# main_board_gen_2.net
KiCad netlist of a schematic drawn in Altium Designer
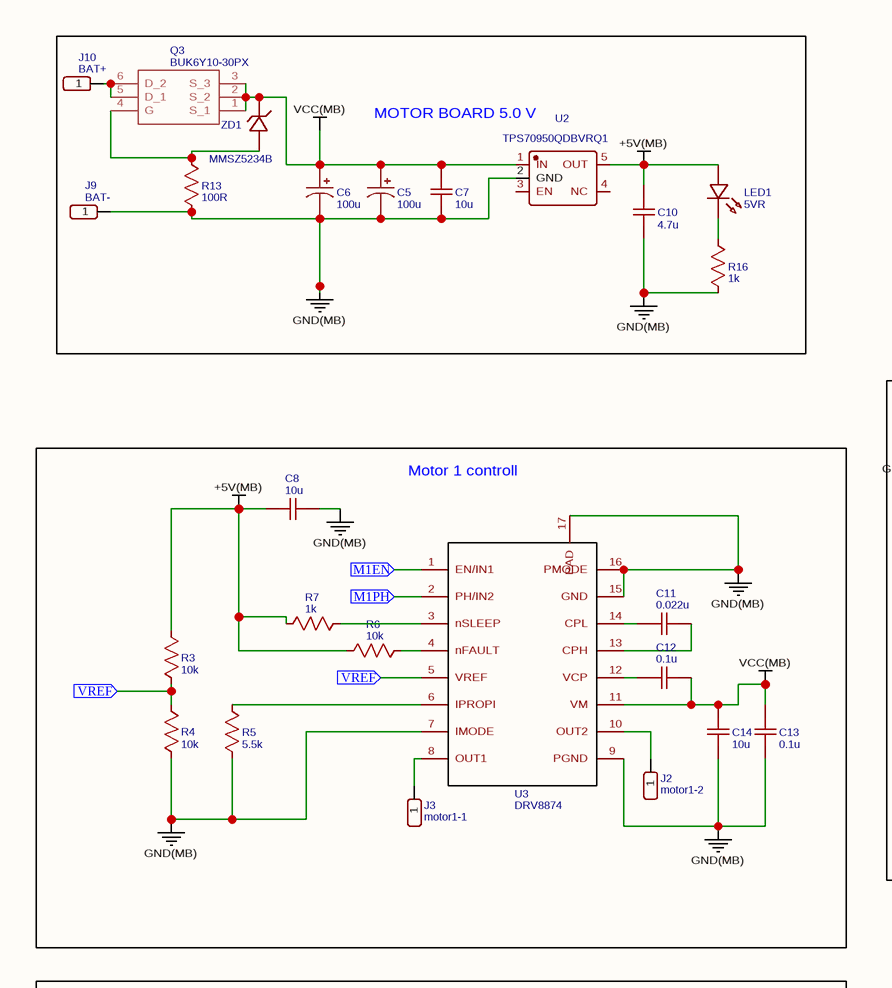
[diagram p0: main_board gen 2.schdoc, top left]
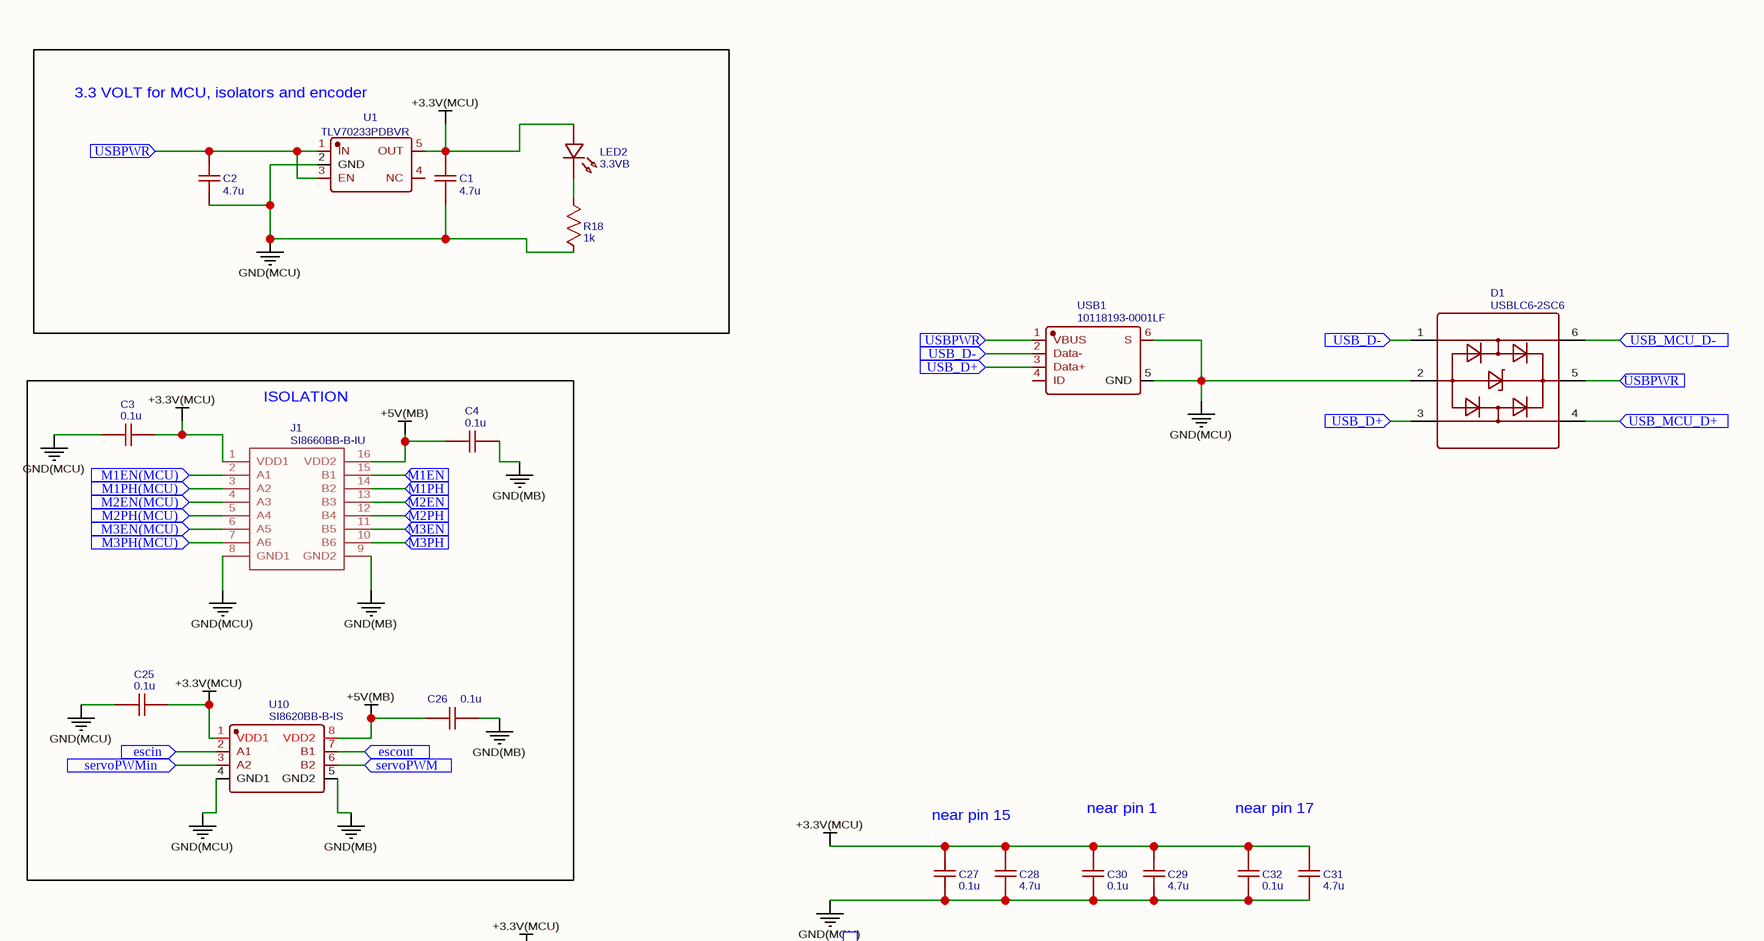
[diagram p1: main_board gen 2.schdoc, top right]
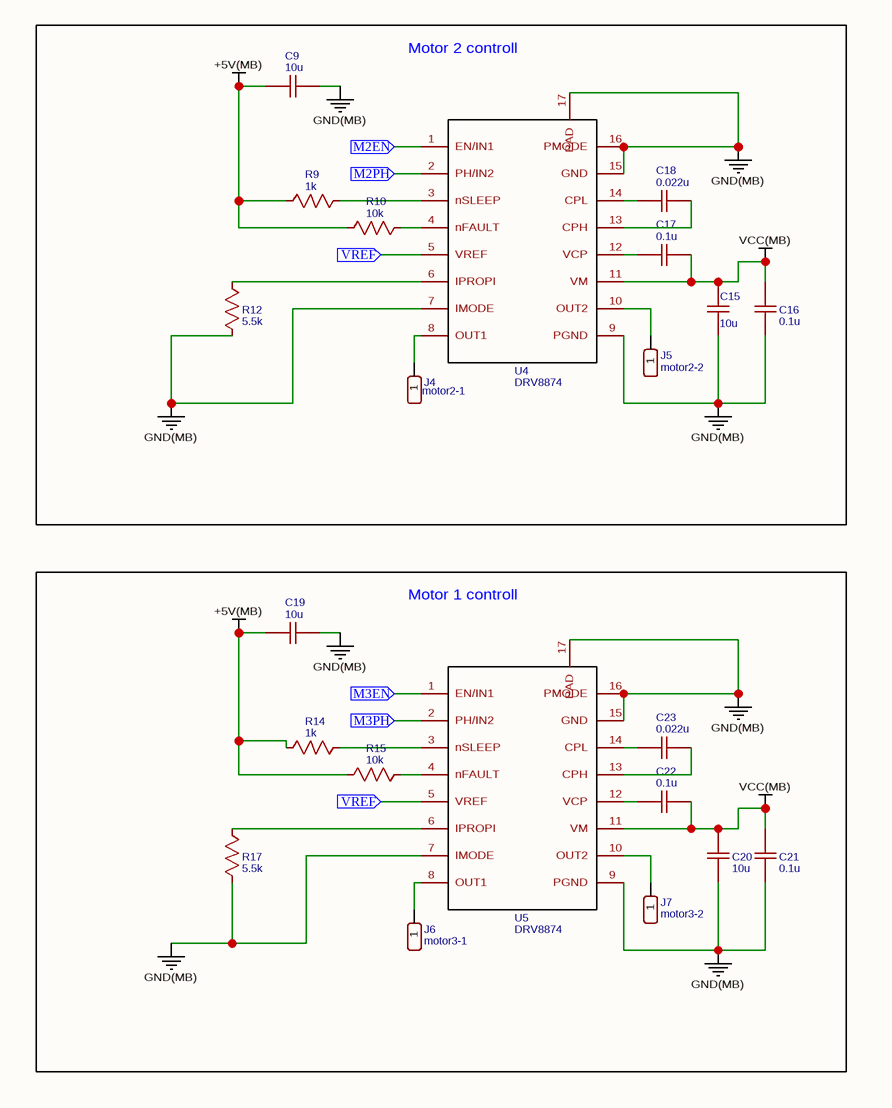
[diagram p2: main_board gen 2.schdoc, bottom left]
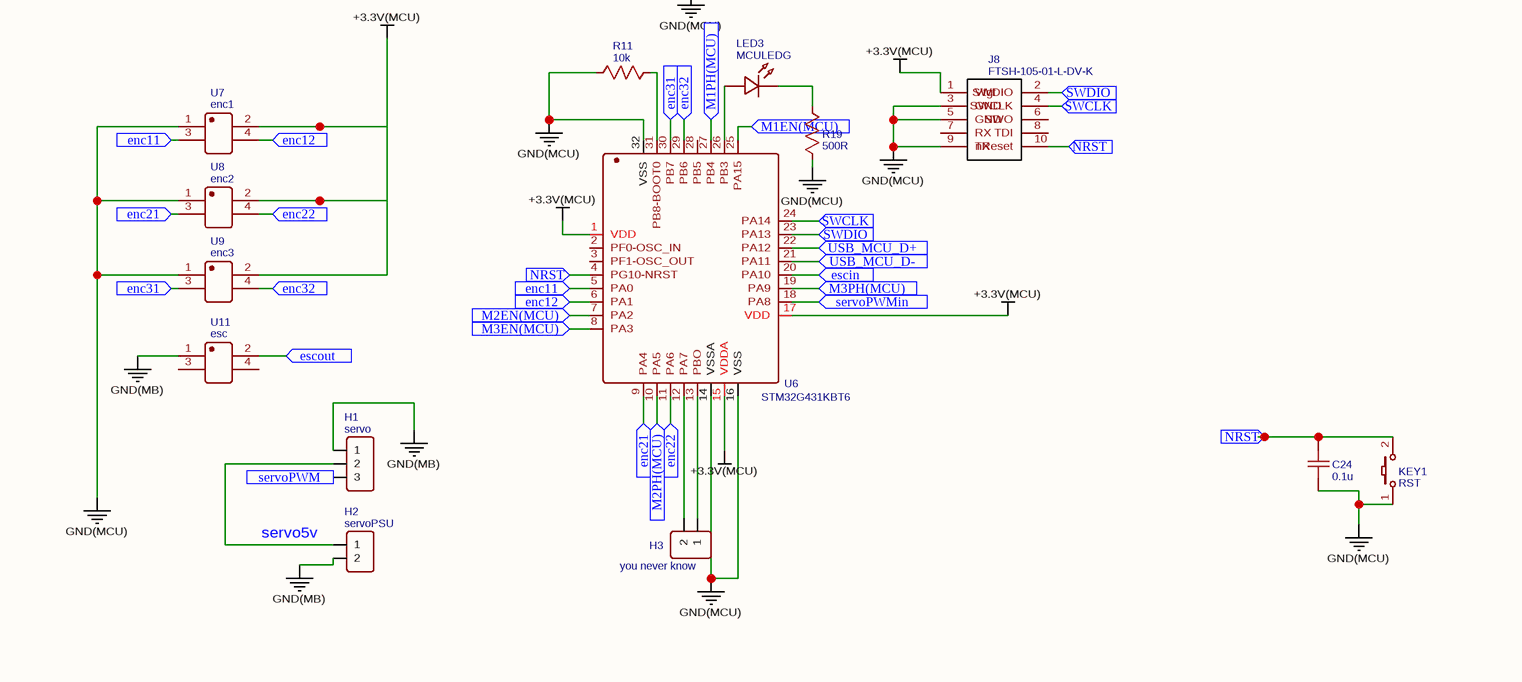
[diagram p3: main_board gen 2.schdoc, bottom right]

(export (version "E")
  (design (tool "Eeschema 10.0.6"))
  (components
    (comp (ref "C1")
      (value "4.7u")
      (fields (field (name "CONTRIBUTOR") "LCEDA_Lib"))
      (libsource (lib "altium-import") (part "root_1_4.7u_"))
    )
    (comp (ref "C2")
      (value "4.7u")
      (fields (field (name "CONTRIBUTOR") "LCEDA_Lib"))
      (libsource (lib "altium-import") (part "root_1_4.7u_"))
    )
    (comp (ref "C3")
      (value "0.1u")
      (fields (field (name "CONTRIBUTOR") "LCEDA_Lib"))
      (libsource (lib "altium-import") (part "root_2_0.1u_"))
    )
    (comp (ref "C4")
      (value "0.1u")
      (fields (field (name "CONTRIBUTOR") "LCEDA_Lib"))
      (libsource (lib "altium-import") (part "root_2_0.1u_"))
    )
    (comp (ref "C5")
      (value "100u")
      (fields (field (name "CONTRIBUTOR") "LCEDA_Lib"))
      (libsource (lib "altium-import") (part "root_3_100u_"))
    )
    (comp (ref "C6")
      (value "100u")
      (fields (field (name "CONTRIBUTOR") "LCEDA_Lib"))
      (libsource (lib "altium-import") (part "root_3_100u_"))
    )
    (comp (ref "C7")
      (value "10u")
      (fields (field (name "CONTRIBUTOR") "LCEDA_Lib"))
      (libsource (lib "altium-import") (part "root_1_10u_"))
    )
    (comp (ref "C8")
      (value "10u")
      (fields (field (name "CONTRIBUTOR") "LCEDA_Lib"))
      (libsource (lib "altium-import") (part "root_0_10u_"))
    )
    (comp (ref "C9")
      (value "10u")
      (fields (field (name "CONTRIBUTOR") "LCEDA_Lib"))
      (libsource (lib "altium-import") (part "root_0_10u_"))
    )
    (comp (ref "C10")
      (value "4.7u")
      (fields (field (name "CONTRIBUTOR") "LCEDA_Lib"))
      (libsource (lib "altium-import") (part "root_1_4.7u_"))
    )
    (comp (ref "C11")
      (value "0.022u")
      (fields (field (name "CONTRIBUTOR") "LCEDA_Lib"))
      (libsource (lib "altium-import") (part "root_0_0.022u_"))
    )
    (comp (ref "C12")
      (value "0.1u")
      (fields (field (name "CONTRIBUTOR") "LCEDA_Lib"))
      (libsource (lib "altium-import") (part "root_0_0.1u_"))
    )
    (comp (ref "C13")
      (value "0.1u")
      (fields (field (name "CONTRIBUTOR") "LCEDA_Lib"))
      (libsource (lib "altium-import") (part "root_1_0.1u_"))
    )
    (comp (ref "C14")
      (value "10u")
      (fields (field (name "CONTRIBUTOR") "LCEDA_Lib"))
      (libsource (lib "altium-import") (part "root_1_10u_"))
    )
    (comp (ref "C15")
      (value "10u")
      (fields (field (name "CONTRIBUTOR") "LCEDA_Lib"))
      (libsource (lib "altium-import") (part "root_1_10u_"))
    )
    (comp (ref "C16")
      (value "0.1u")
      (fields (field (name "CONTRIBUTOR") "LCEDA_Lib"))
      (libsource (lib "altium-import") (part "root_1_0.1u_"))
    )
    (comp (ref "C17")
      (value "0.1u")
      (fields (field (name "CONTRIBUTOR") "LCEDA_Lib"))
      (libsource (lib "altium-import") (part "root_0_0.1u_"))
    )
    (comp (ref "C18")
      (value "0.022u")
      (fields (field (name "CONTRIBUTOR") "LCEDA_Lib"))
      (libsource (lib "altium-import") (part "root_0_0.022u_"))
    )
    (comp (ref "C19")
      (value "10u")
      (fields (field (name "CONTRIBUTOR") "LCEDA_Lib"))
      (libsource (lib "altium-import") (part "root_0_10u_"))
    )
    (comp (ref "C20")
      (value "10u")
      (fields (field (name "CONTRIBUTOR") "LCEDA_Lib"))
      (libsource (lib "altium-import") (part "root_1_10u_"))
    )
    (comp (ref "C21")
      (value "0.1u")
      (fields (field (name "CONTRIBUTOR") "LCEDA_Lib"))
      (libsource (lib "altium-import") (part "root_1_0.1u_"))
    )
    (comp (ref "C22")
      (value "0.1u")
      (fields (field (name "CONTRIBUTOR") "LCEDA_Lib"))
      (libsource (lib "altium-import") (part "root_0_0.1u_"))
    )
    (comp (ref "C23")
      (value "0.022u")
      (fields (field (name "CONTRIBUTOR") "LCEDA_Lib"))
      (libsource (lib "altium-import") (part "root_0_0.022u_"))
    )
    (comp (ref "C24")
      (value "0.1u")
      (fields (field (name "CONTRIBUTOR") "LCEDA_Lib"))
      (libsource (lib "altium-import") (part "root_1_0.1u_"))
    )
    (comp (ref "C25")
      (value "0.1u")
      (fields (field (name "CONTRIBUTOR") "LCEDA_Lib"))
      (libsource (lib "altium-import") (part "root_2_0.1u_"))
    )
    (comp (ref "C26")
      (value "0.1u")
      (fields (field (name "CONTRIBUTOR") "LCEDA_Lib"))
      (libsource (lib "altium-import") (part "root_2_0.1u_"))
    )
    (comp (ref "C27")
      (value "0.1u")
      (fields (field (name "CONTRIBUTOR") "LCEDA_Lib"))
      (libsource (lib "altium-import") (part "root_1_0.1u_"))
    )
    (comp (ref "C28")
      (value "4.7u")
      (fields (field (name "CONTRIBUTOR") "LCEDA_Lib"))
      (libsource (lib "altium-import") (part "root_1_4.7u_"))
    )
    (comp (ref "C29")
      (value "4.7u")
      (fields (field (name "CONTRIBUTOR") "LCEDA_Lib"))
      (libsource (lib "altium-import") (part "root_1_4.7u_"))
    )
    (comp (ref "C30")
      (value "0.1u")
      (fields (field (name "CONTRIBUTOR") "LCEDA_Lib"))
      (libsource (lib "altium-import") (part "root_1_0.1u_"))
    )
    (comp (ref "C31")
      (value "4.7u")
      (fields (field (name "CONTRIBUTOR") "LCEDA_Lib"))
      (libsource (lib "altium-import") (part "root_1_4.7u_"))
    )
    (comp (ref "C32")
      (value "0.1u")
      (fields (field (name "CONTRIBUTOR") "LCEDA_Lib"))
      (libsource (lib "altium-import") (part "root_1_0.1u_"))
    )
    (comp (ref "D1")
      (value "USBLC6-2SC6")
      (fields (field (name "BOM_SUPPLIER PART") "C7519"))
      (libsource (lib "altium-import") (part "root_0_USBLC6-2SC6_"))
    )
    (comp (ref "H1")
      (value "servo")
      (fields (field (name "BOM_SUPPLIER PART") "C146690") (field (name "CONTRIBUTOR") "LCEDA_Lib"))
      (libsource (lib "altium-import") (part "root_0_servo_"))
    )
    (comp (ref "H2")
      (value "servoPSU")
      (fields (field (name "BOM_SUPPLIER PART") "C49661") (field (name "CONTRIBUTOR") "LCEDA_Lib"))
      (libsource (lib "altium-import") (part "root_0_servoPSU_"))
    )
    (comp (ref "H3")
      (value "you never know")
      (fields (field (name "BOM_SUPPLIER PART") "C49661") (field (name "CONTRIBUTOR") "LCEDA_Lib"))
      (libsource (lib "altium-import") (part "root_3_you never know_"))
    )
    (comp (ref "J1")
      (value "SI8660BB-B-IU")
      (fields (field (name "CONTRIBUTOR") "david rizhinashvili"))
      (libsource (lib "altium-import") (part "root_0_SI8660BB-B-IU_"))
    )
    (comp (ref "J2")
      (value "motor1-2")
      (fields (field (name "BOM_SUPPLIER PART") "C81276") (field (name "CONTRIBUTOR") "LCEDA_Lib"))
      (libsource (lib "altium-import") (part "root_3_motor1-2_"))
    )
    (comp (ref "J3")
      (value "motor1-1")
      (fields (field (name "BOM_SUPPLIER PART") "C81276") (field (name "CONTRIBUTOR") "LCEDA_Lib"))
      (libsource (lib "altium-import") (part "root_3_motor1-1_"))
    )
    (comp (ref "J4")
      (value "motor2-1")
      (fields (field (name "BOM_SUPPLIER PART") "C81276") (field (name "CONTRIBUTOR") "LCEDA_Lib"))
      (libsource (lib "altium-import") (part "root_3_motor2-1_"))
    )
    (comp (ref "J5")
      (value "motor2-2")
      (fields (field (name "BOM_SUPPLIER PART") "C81276") (field (name "CONTRIBUTOR") "LCEDA_Lib"))
      (libsource (lib "altium-import") (part "root_3_motor2-2_"))
    )
    (comp (ref "J6")
      (value "motor3-1")
      (fields (field (name "BOM_SUPPLIER PART") "C81276") (field (name "CONTRIBUTOR") "LCEDA_Lib"))
      (libsource (lib "altium-import") (part "root_3_motor3-1_"))
    )
    (comp (ref "J7")
      (value "motor3-2")
      (fields (field (name "BOM_SUPPLIER PART") "C81276") (field (name "CONTRIBUTOR") "LCEDA_Lib"))
      (libsource (lib "altium-import") (part "root_3_motor3-2_"))
    )
    (comp (ref "J8")
      (value "FTSH-105-01-L-DV-K")
      (fields (field (name "BOM_SUPPLIER PART") "SAM8799-ND") (field (name "CONTRIBUTOR") "OBC Gang"))
      (libsource (lib "altium-import") (part "root_0_FTSH-105-01-L-DV-K_"))
    )
    (comp (ref "J9")
      (value "BAT-")
      (fields (field (name "BOM_SUPPLIER PART") "C81276") (field (name "CONTRIBUTOR") "LCEDA_Lib"))
      (libsource (lib "altium-import") (part "root_2_BAT-_"))
    )
    (comp (ref "J10")
      (value "BAT+")
      (fields (field (name "BOM_SUPPLIER PART") "C81276") (field (name "CONTRIBUTOR") "LCEDA_Lib"))
      (libsource (lib "altium-import") (part "root_2_BAT+_"))
    )
    (comp (ref "KEY1")
      (value "RST")
      (fields
        (field (name "BOM_SUPPLIER PART") "C118141")
        (field (name "BOM_MANUFACTURER PART") "K2-1107ST-A4SW-06")
        (field (name "CONTRIBUTOR") "LCEDA_Lib")
      )
      (libsource (lib "altium-import") (part "root_1_RST_"))
    )
    (comp (ref "LED1")
      (value "5VR")
      (fields
        (field (name "BOM_MANUFACTURER PART") "19-217/R6C-AL1M2VY/3T")
        (field (name "BOM_SUPPLIER PART") "C72044")
        (field (name "CONTRIBUTOR") "LCEDA_01")
      )
      (libsource (lib "altium-import") (part "root_3_5VR_"))
    )
    (comp (ref "LED2")
      (value "3.3VB")
      (fields
        (field (name "BOM_MANUFACTURER PART") "19-217/R6C-AL1M2VY/3T")
        (field (name "BOM_SUPPLIER PART") "C72044")
        (field (name "CONTRIBUTOR") "LCEDA_01")
      )
      (libsource (lib "altium-import") (part "root_3_3.3VB_"))
    )
    (comp (ref "LED3")
      (value "MCULEDG")
      (fields
        (field (name "BOM_MANUFACTURER PART") "19-217/R6C-AL1M2VY/3T")
        (field (name "BOM_SUPPLIER PART") "C72044")
        (field (name "CONTRIBUTOR") "LCEDA_01")
      )
      (libsource (lib "altium-import") (part "root_0_MCULEDG_"))
    )
    (comp (ref "Q3")
      (value "BUK6Y10-30PX")
      (fields (field (name "CONTRIBUTOR") "david rizhinashvili"))
      (libsource (lib "altium-import") (part "root_2_BUK6Y10-30PX_"))
    )
    (comp (ref "R3")
      (value "10k")
      (fields (field (name "CONTRIBUTOR") "LCEDA_Lib"))
      (libsource (lib "altium-import") (part "root_3_10k_"))
    )
    (comp (ref "R4")
      (value "10k")
      (fields (field (name "CONTRIBUTOR") "LCEDA_Lib"))
      (libsource (lib "altium-import") (part "root_3_10k_"))
    )
    (comp (ref "R5")
      (value "5.5k")
      (fields (field (name "CONTRIBUTOR") "LCEDA_Lib"))
      (libsource (lib "altium-import") (part "root_1_5.5k_"))
    )
    (comp (ref "R6")
      (value "10k")
      (fields (field (name "CONTRIBUTOR") "LCEDA_Lib"))
      (libsource (lib "altium-import") (part "root_0_10k_"))
    )
    (comp (ref "R7")
      (value "1k")
      (fields (field (name "CONTRIBUTOR") "LCEDA_Lib"))
      (libsource (lib "altium-import") (part "root_0_1k_"))
    )
    (comp (ref "R9")
      (value "1k")
      (fields (field (name "CONTRIBUTOR") "LCEDA_Lib"))
      (libsource (lib "altium-import") (part "root_0_1k_"))
    )
    (comp (ref "R10")
      (value "10k")
      (fields (field (name "CONTRIBUTOR") "LCEDA_Lib"))
      (libsource (lib "altium-import") (part "root_0_10k_"))
    )
    (comp (ref "R11")
      (value "10k")
      (fields (field (name "CONTRIBUTOR") "LCEDA_Lib"))
      (libsource (lib "altium-import") (part "root_0_10k_"))
    )
    (comp (ref "R12")
      (value "5.5k")
      (fields (field (name "CONTRIBUTOR") "LCEDA_Lib"))
      (libsource (lib "altium-import") (part "root_1_5.5k_"))
    )
    (comp (ref "R13")
      (value "100R")
      (fields (field (name "CONTRIBUTOR") "LCEDA_Lib"))
      (libsource (lib "altium-import") (part "root_1_100R_"))
    )
    (comp (ref "R14")
      (value "1k")
      (fields (field (name "CONTRIBUTOR") "LCEDA_Lib"))
      (libsource (lib "altium-import") (part "root_0_1k_"))
    )
    (comp (ref "R15")
      (value "10k")
      (fields (field (name "CONTRIBUTOR") "LCEDA_Lib"))
      (libsource (lib "altium-import") (part "root_0_10k_"))
    )
    (comp (ref "R16")
      (value "1k")
      (fields (field (name "CONTRIBUTOR") "LCEDA_Lib"))
      (libsource (lib "altium-import") (part "root_1_1k_"))
    )
    (comp (ref "R17")
      (value "5.5k")
      (fields (field (name "CONTRIBUTOR") "LCEDA_Lib"))
      (libsource (lib "altium-import") (part "root_1_5.5k_"))
    )
    (comp (ref "R18")
      (value "1k")
      (fields (field (name "CONTRIBUTOR") "LCEDA_Lib"))
      (libsource (lib "altium-import") (part "root_1_1k_"))
    )
    (comp (ref "R19")
      (value "500R")
      (fields (field (name "CONTRIBUTOR") "LCEDA_Lib"))
      (libsource (lib "altium-import") (part "root_1_500R_"))
    )
    (comp (ref "U1")
      (value "TLV70233PDBVR")
      (fields (field (name "BOM_SUPPLIER PART") "C123134") (field (name "CONTRIBUTOR") "LCSC"))
      (libsource (lib "altium-import") (part "root_0_TLV70233PDBVR_"))
    )
    (comp (ref "U2")
      (value "TPS70950QDBVRQ1")
      (fields (field (name "BOM_SUPPLIER PART") "C485909") (field (name "CONTRIBUTOR") "LCSC"))
      (libsource (lib "altium-import") (part "root_0_TPS70950QDBVRQ1_"))
    )
    (comp (ref "U3")
      (value "DRV8874")
      (fields (field (name "CONTRIBUTOR") "Plexus"))
      (libsource (lib "altium-import") (part "root_0_DRV8874_"))
    )
    (comp (ref "U4")
      (value "DRV8874")
      (fields (field (name "CONTRIBUTOR") "Plexus"))
      (libsource (lib "altium-import") (part "root_0_DRV8874_"))
    )
    (comp (ref "U5")
      (value "DRV8874")
      (fields (field (name "CONTRIBUTOR") "Plexus"))
      (libsource (lib "altium-import") (part "root_0_DRV8874_"))
    )
    (comp (ref "U6")
      (value "STM32G431KBT6")
      (fields (field (name "BOM_SUPPLIER PART") "C529357") (field (name "CONTRIBUTOR") "LCSC"))
      (libsource (lib "altium-import") (part "root_0_STM32G431KBT6_"))
    )
    (comp (ref "U7")
      (value "enc1")
      (fields
        (field (name "BOM_SUPPLIER PART") "C306232")
        (field (name "BOM_MANUFACTURER PART") "215079-4")
        (field (name "CONTRIBUTOR") "LCSC")
      )
      (libsource (lib "altium-import") (part "root_0_enc1_"))
    )
    (comp (ref "U8")
      (value "enc2")
      (fields
        (field (name "BOM_SUPPLIER PART") "C306232")
        (field (name "BOM_MANUFACTURER PART") "215079-4")
        (field (name "CONTRIBUTOR") "LCSC")
      )
      (libsource (lib "altium-import") (part "root_0_enc2_"))
    )
    (comp (ref "U9")
      (value "enc3")
      (fields
        (field (name "BOM_SUPPLIER PART") "C306232")
        (field (name "BOM_MANUFACTURER PART") "215079-4")
        (field (name "CONTRIBUTOR") "LCSC")
      )
      (libsource (lib "altium-import") (part "root_0_enc3_"))
    )
    (comp (ref "U10")
      (value "SI8620BB-B-IS")
      (fields (field (name "BOM_SUPPLIER PART") "C430264") (field (name "CONTRIBUTOR") "LCSC"))
      (libsource (lib "altium-import") (part "root_0_SI8620BB-B-IS_"))
    )
    (comp (ref "U11")
      (value "esc")
      (fields
        (field (name "BOM_SUPPLIER PART") "C306232")
        (field (name "BOM_MANUFACTURER PART") "215079-4")
        (field (name "CONTRIBUTOR") "LCSC")
      )
      (libsource (lib "altium-import") (part "root_0_esc_"))
    )
    (comp (ref "USB1")
      (value "10118193-0001LF")
      (fields (field (name "BOM_SUPPLIER PART") "C132562") (field (name "CONTRIBUTOR") "LCSC"))
      (libsource (lib "altium-import") (part "root_0_10118193-0001LF_"))
    )
    (comp (ref "ZD1")
      (value "MMSZ5234B")
      (fields (field (name "BOM_SUPPLIER PART") "C21556"))
      (libsource (lib "altium-import") (part "root_3_MMSZ5234B_"))
    )
  )
  (nets
    (net (code "1") (name "+3.3V(MCU)") (class "Default")
      (node (ref "C1") (pin "2") (pinfunction "2_2") (pintype "passive"))
      (node (ref "C25") (pin "1") (pinfunction "1_1") (pintype "passive"))
      (node (ref "C27") (pin "2") (pinfunction "2_2") (pintype "passive"))
      (node (ref "C28") (pin "2") (pinfunction "2_2") (pintype "passive"))
      (node (ref "C29") (pin "2") (pinfunction "2_2") (pintype "passive"))
      (node (ref "C3") (pin "1") (pinfunction "1_1") (pintype "passive"))
      (node (ref "C30") (pin "2") (pinfunction "2_2") (pintype "passive"))
      (node (ref "C31") (pin "2") (pinfunction "2_2") (pintype "passive"))
      (node (ref "C32") (pin "2") (pinfunction "2_2") (pintype "passive"))
      (node (ref "J1") (pin "1") (pinfunction "VDD1_1") (pintype "passive"))
      (node (ref "J8") (pin "1") (pinfunction "Vtgt_1") (pintype "passive"))
      (node (ref "LED2") (pin "1") (pinfunction "1_1") (pintype "passive"))
      (node (ref "U1") (pin "5") (pinfunction "OUT_5") (pintype "passive"))
      (node (ref "U10") (pin "1") (pinfunction "VDD1_1") (pintype "passive"))
      (node (ref "U6") (pin "1") (pinfunction "VDD_1") (pintype "passive"))
      (node (ref "U6") (pin "15") (pinfunction "VDDA_15") (pintype "passive"))
      (node (ref "U6") (pin "17") (pinfunction "VDD_17") (pintype "passive"))
      (node (ref "U7") (pin "2") (pinfunction "2_2") (pintype "passive"))
      (node (ref "U8") (pin "2") (pinfunction "2_2") (pintype "passive"))
      (node (ref "U9") (pin "2") (pinfunction "2_2") (pintype "passive"))
    )
    (net (code "2") (name "+5V(MB)") (class "Default")
      (node (ref "C10") (pin "2") (pinfunction "2_2") (pintype "passive"))
      (node (ref "C19") (pin "1") (pinfunction "1_1") (pintype "passive"))
      (node (ref "C26") (pin "2") (pinfunction "2_2") (pintype "passive"))
      (node (ref "C4") (pin "2") (pinfunction "2_2") (pintype "passive"))
      (node (ref "C8") (pin "1") (pinfunction "1_1") (pintype "passive"))
      (node (ref "C9") (pin "1") (pinfunction "1_1") (pintype "passive"))
      (node (ref "J1") (pin "16") (pinfunction "VDD2_16") (pintype "passive"))
      (node (ref "LED1") (pin "1") (pinfunction "1_1") (pintype "passive"))
      (node (ref "R10") (pin "1") (pinfunction "1_1") (pintype "passive"))
      (node (ref "R14") (pin "1") (pinfunction "1_1") (pintype "passive"))
      (node (ref "R15") (pin "1") (pinfunction "1_1") (pintype "passive"))
      (node (ref "R3") (pin "1") (pinfunction "1_1") (pintype "passive"))
      (node (ref "R6") (pin "1") (pinfunction "1_1") (pintype "passive"))
      (node (ref "R7") (pin "1") (pinfunction "1_1") (pintype "passive"))
      (node (ref "R9") (pin "1") (pinfunction "1_1") (pintype "passive"))
      (node (ref "U10") (pin "8") (pinfunction "VDD2_8") (pintype "passive"))
      (node (ref "U2") (pin "5") (pinfunction "OUT_5") (pintype "passive"))
    )
    (net (code "3") (name "/M1EN") (class "Default")
      (node (ref "J1") (pin "15") (pinfunction "B1_15") (pintype "passive"))
      (node (ref "U3") (pin "1") (pinfunction "EN/IN1_1") (pintype "passive"))
    )
    (net (code "4") (name "/M1EN(MCU)") (class "Default")
      (node (ref "J1") (pin "2") (pinfunction "A1_2") (pintype "passive"))
      (node (ref "U6") (pin "25") (pinfunction "PA15_25") (pintype "passive"))
    )
    (net (code "5") (name "/M1PH") (class "Default")
      (node (ref "J1") (pin "14") (pinfunction "B2_14") (pintype "passive"))
      (node (ref "U3") (pin "2") (pinfunction "PH/IN2_2") (pintype "passive"))
    )
    (net (code "6") (name "/M1PH(MCU)") (class "Default")
      (node (ref "J1") (pin "3") (pinfunction "A2_3") (pintype "passive"))
      (node (ref "U6") (pin "27") (pinfunction "PB4_27") (pintype "passive"))
    )
    (net (code "7") (name "/M2EN") (class "Default")
      (node (ref "J1") (pin "13") (pinfunction "B3_13") (pintype "passive"))
      (node (ref "U4") (pin "1") (pinfunction "EN/IN1_1") (pintype "passive"))
    )
    (net (code "8") (name "/M2EN(MCU)") (class "Default")
      (node (ref "J1") (pin "4") (pinfunction "A3_4") (pintype "passive"))
      (node (ref "U6") (pin "7") (pinfunction "PA2_7") (pintype "passive"))
    )
    (net (code "9") (name "/M2PH") (class "Default")
      (node (ref "J1") (pin "12") (pinfunction "B4_12") (pintype "passive"))
      (node (ref "U4") (pin "2") (pinfunction "PH/IN2_2") (pintype "passive"))
    )
    (net (code "10") (name "/M2PH(MCU)") (class "Default")
      (node (ref "J1") (pin "5") (pinfunction "A4_5") (pintype "passive"))
      (node (ref "U6") (pin "10") (pinfunction "PA5_10") (pintype "passive"))
    )
    (net (code "11") (name "/M3EN") (class "Default")
      (node (ref "J1") (pin "11") (pinfunction "B5_11") (pintype "passive"))
      (node (ref "U5") (pin "1") (pinfunction "EN/IN1_1") (pintype "passive"))
    )
    (net (code "12") (name "/M3EN(MCU)") (class "Default")
      (node (ref "J1") (pin "6") (pinfunction "A5_6") (pintype "passive"))
      (node (ref "U6") (pin "8") (pinfunction "PA3_8") (pintype "passive"))
    )
    (net (code "13") (name "/M3PH") (class "Default")
      (node (ref "J1") (pin "10") (pinfunction "B6_10") (pintype "passive"))
      (node (ref "U5") (pin "2") (pinfunction "PH/IN2_2") (pintype "passive"))
    )
    (net (code "14") (name "/M3PH(MCU)") (class "Default")
      (node (ref "J1") (pin "7") (pinfunction "A6_7") (pintype "passive"))
      (node (ref "U6") (pin "19") (pinfunction "PA9_19") (pintype "passive"))
    )
    (net (code "15") (name "/NRST") (class "Default")
      (node (ref "C24") (pin "2") (pinfunction "2_2") (pintype "passive"))
      (node (ref "J8") (pin "10") (pinfunction "nReset_10") (pintype "passive"))
      (node (ref "KEY1") (pin "2") (pinfunction "2_2") (pintype "passive"))
      (node (ref "U6") (pin "4") (pinfunction "PG10-NRST_4") (pintype "passive"))
    )
    (net (code "16") (name "/SWCLK") (class "Default")
      (node (ref "J8") (pin "4") (pinfunction "SWCLK_4") (pintype "passive"))
      (node (ref "U6") (pin "24") (pinfunction "PA14_24") (pintype "passive"))
    )
    (net (code "17") (name "/SWDIO") (class "Default")
      (node (ref "J8") (pin "2") (pinfunction "SWDIO_2") (pintype "passive"))
      (node (ref "U6") (pin "23") (pinfunction "PA13_23") (pintype "passive"))
    )
    (net (code "18") (name "/USBPWR") (class "Default")
      (node (ref "C2") (pin "2") (pinfunction "2_2") (pintype "passive"))
      (node (ref "D1") (pin "5") (pinfunction "5_5") (pintype "passive"))
      (node (ref "U1") (pin "1") (pinfunction "IN_1") (pintype "passive"))
      (node (ref "U1") (pin "3") (pinfunction "EN_3") (pintype "passive"))
      (node (ref "USB1") (pin "1") (pinfunction "VBUS_1") (pintype "passive"))
    )
    (net (code "19") (name "/USB_D+") (class "Default")
      (node (ref "D1") (pin "3") (pinfunction "3_3") (pintype "passive"))
      (node (ref "USB1") (pin "3") (pinfunction "Data+_3") (pintype "passive"))
    )
    (net (code "20") (name "/USB_D-") (class "Default")
      (node (ref "D1") (pin "1") (pinfunction "1_1") (pintype "passive"))
      (node (ref "USB1") (pin "2") (pinfunction "Data-_2") (pintype "passive"))
    )
    (net (code "21") (name "/USB_MCU_D+") (class "Default")
      (node (ref "D1") (pin "4") (pinfunction "4_4") (pintype "passive"))
      (node (ref "U6") (pin "22") (pinfunction "PA12_22") (pintype "passive"))
    )
    (net (code "22") (name "/USB_MCU_D-") (class "Default")
      (node (ref "D1") (pin "6") (pinfunction "6_6") (pintype "passive"))
      (node (ref "U6") (pin "21") (pinfunction "PA11_21") (pintype "passive"))
    )
    (net (code "23") (name "/VREF") (class "Default")
      (node (ref "R3") (pin "2") (pinfunction "2_2") (pintype "passive"))
      (node (ref "R4") (pin "1") (pinfunction "1_1") (pintype "passive"))
      (node (ref "U3") (pin "5") (pinfunction "VREF_5") (pintype "passive"))
      (node (ref "U4") (pin "5") (pinfunction "VREF_5") (pintype "passive"))
      (node (ref "U5") (pin "5") (pinfunction "VREF_5") (pintype "passive"))
    )
    (net (code "24") (name "/enc11") (class "Default")
      (node (ref "U6") (pin "5") (pinfunction "PA0_5") (pintype "passive"))
      (node (ref "U7") (pin "3") (pinfunction "3_3") (pintype "passive"))
    )
    (net (code "25") (name "/enc12") (class "Default")
      (node (ref "U6") (pin "6") (pinfunction "PA1_6") (pintype "passive"))
      (node (ref "U7") (pin "4") (pinfunction "4_4") (pintype "passive"))
    )
    (net (code "26") (name "/enc21") (class "Default")
      (node (ref "U6") (pin "9") (pinfunction "PA4_9") (pintype "passive"))
      (node (ref "U8") (pin "3") (pinfunction "3_3") (pintype "passive"))
    )
    (net (code "27") (name "/enc22") (class "Default")
      (node (ref "U6") (pin "11") (pinfunction "PA6_11") (pintype "passive"))
      (node (ref "U8") (pin "4") (pinfunction "4_4") (pintype "passive"))
    )
    (net (code "28") (name "/enc31") (class "Default")
      (node (ref "U6") (pin "30") (pinfunction "PB7_30") (pintype "passive"))
      (node (ref "U9") (pin "3") (pinfunction "3_3") (pintype "passive"))
    )
    (net (code "29") (name "/enc32") (class "Default")
      (node (ref "U6") (pin "29") (pinfunction "PB6_29") (pintype "passive"))
      (node (ref "U9") (pin "4") (pinfunction "4_4") (pintype "passive"))
    )
    (net (code "30") (name "/escin") (class "Default")
      (node (ref "U10") (pin "2") (pinfunction "A1_2") (pintype "passive"))
      (node (ref "U6") (pin "20") (pinfunction "PA10_20") (pintype "passive"))
    )
    (net (code "31") (name "/escout") (class "Default")
      (node (ref "U10") (pin "7") (pinfunction "B1_7") (pintype "passive"))
      (node (ref "U11") (pin "2") (pinfunction "2_2") (pintype "passive"))
    )
    (net (code "32") (name "/servoPWM") (class "Default")
      (node (ref "H1") (pin "3") (pinfunction "3_3") (pintype "passive"))
      (node (ref "U10") (pin "6") (pinfunction "B2_6") (pintype "passive"))
    )
    (net (code "33") (name "/servoPWMin") (class "Default")
      (node (ref "U10") (pin "3") (pinfunction "A2_3") (pintype "passive"))
      (node (ref "U6") (pin "18") (pinfunction "PA8_18") (pintype "passive"))
    )
    (net (code "34") (name "GND(MB)") (class "Default")
      (node (ref "C10") (pin "1") (pinfunction "1_1") (pintype "passive"))
      (node (ref "C13") (pin "1") (pinfunction "1_1") (pintype "passive"))
      (node (ref "C14") (pin "1") (pinfunction "1_1") (pintype "passive"))
      (node (ref "C15") (pin "1") (pinfunction "1_1") (pintype "passive"))
      (node (ref "C16") (pin "1") (pinfunction "1_1") (pintype "passive"))
      (node (ref "C19") (pin "2") (pinfunction "2_2") (pintype "passive"))
      (node (ref "C20") (pin "1") (pinfunction "1_1") (pintype "passive"))
      (node (ref "C21") (pin "1") (pinfunction "1_1") (pintype "passive"))
      (node (ref "C26") (pin "1") (pinfunction "1_1") (pintype "passive"))
      (node (ref "C4") (pin "1") (pinfunction "1_1") (pintype "passive"))
      (node (ref "C5") (pin "2") (pinfunction "2_2") (pintype "passive"))
      (node (ref "C6") (pin "2") (pinfunction "2_2") (pintype "passive"))
      (node (ref "C7") (pin "1") (pinfunction "1_1") (pintype "passive"))
      (node (ref "C8") (pin "2") (pinfunction "2_2") (pintype "passive"))
      (node (ref "C9") (pin "2") (pinfunction "2_2") (pintype "passive"))
      (node (ref "H1") (pin "1") (pinfunction "1_1") (pintype "passive"))
      (node (ref "H2") (pin "2") (pinfunction "2_2") (pintype "passive"))
      (node (ref "J1") (pin "9") (pinfunction "GND2_9") (pintype "passive"))
      (node (ref "J9") (pin "1") (pinfunction "1_1") (pintype "passive"))
      (node (ref "R12") (pin "1") (pinfunction "1_1") (pintype "passive"))
      (node (ref "R13") (pin "1") (pinfunction "1_1") (pintype "passive"))
      (node (ref "R16") (pin "1") (pinfunction "1_1") (pintype "passive"))
      (node (ref "R17") (pin "1") (pinfunction "1_1") (pintype "passive"))
      (node (ref "R4") (pin "2") (pinfunction "2_2") (pintype "passive"))
      (node (ref "R5") (pin "1") (pinfunction "1_1") (pintype "passive"))
      (node (ref "U10") (pin "5") (pinfunction "GND2_5") (pintype "passive"))
      (node (ref "U11") (pin "1") (pinfunction "1_1") (pintype "passive"))
      (node (ref "U2") (pin "2") (pinfunction "GND_2") (pintype "passive"))
      (node (ref "U3") (pin "15") (pinfunction "GND_15") (pintype "passive"))
      (node (ref "U3") (pin "16") (pinfunction "PMODE_16") (pintype "passive"))
      (node (ref "U3") (pin "17") (pinfunction "PAD_17") (pintype "passive"))
      (node (ref "U3") (pin "7") (pinfunction "IMODE_7") (pintype "passive"))
      (node (ref "U3") (pin "9") (pinfunction "PGND_9") (pintype "passive"))
      (node (ref "U4") (pin "15") (pinfunction "GND_15") (pintype "passive"))
      (node (ref "U4") (pin "16") (pinfunction "PMODE_16") (pintype "passive"))
      (node (ref "U4") (pin "17") (pinfunction "PAD_17") (pintype "passive"))
      (node (ref "U4") (pin "7") (pinfunction "IMODE_7") (pintype "passive"))
      (node (ref "U4") (pin "9") (pinfunction "PGND_9") (pintype "passive"))
      (node (ref "U5") (pin "15") (pinfunction "GND_15") (pintype "passive"))
      (node (ref "U5") (pin "16") (pinfunction "PMODE_16") (pintype "passive"))
      (node (ref "U5") (pin "17") (pinfunction "PAD_17") (pintype "passive"))
      (node (ref "U5") (pin "7") (pinfunction "IMODE_7") (pintype "passive"))
      (node (ref "U5") (pin "9") (pinfunction "PGND_9") (pintype "passive"))
    )
    (net (code "35") (name "GND(MCU)") (class "Default")
      (node (ref "C1") (pin "1") (pinfunction "1_1") (pintype "passive"))
      (node (ref "C2") (pin "1") (pinfunction "1_1") (pintype "passive"))
      (node (ref "C24") (pin "1") (pinfunction "1_1") (pintype "passive"))
      (node (ref "C25") (pin "2") (pinfunction "2_2") (pintype "passive"))
      (node (ref "C27") (pin "1") (pinfunction "1_1") (pintype "passive"))
      (node (ref "C28") (pin "1") (pinfunction "1_1") (pintype "passive"))
      (node (ref "C29") (pin "1") (pinfunction "1_1") (pintype "passive"))
      (node (ref "C3") (pin "2") (pinfunction "2_2") (pintype "passive"))
      (node (ref "C30") (pin "1") (pinfunction "1_1") (pintype "passive"))
      (node (ref "C31") (pin "1") (pinfunction "1_1") (pintype "passive"))
      (node (ref "C32") (pin "1") (pinfunction "1_1") (pintype "passive"))
      (node (ref "D1") (pin "2") (pinfunction "2_2") (pintype "passive"))
      (node (ref "J1") (pin "8") (pinfunction "GND1_8") (pintype "passive"))
      (node (ref "J8") (pin "3") (pinfunction "GND_3") (pintype "passive"))
      (node (ref "J8") (pin "5") (pinfunction "GND_5") (pintype "passive"))
      (node (ref "J8") (pin "9") (pinfunction "TX_9") (pintype "passive"))
      (node (ref "KEY1") (pin "1") (pinfunction "1_1") (pintype "passive"))
      (node (ref "R11") (pin "1") (pinfunction "1_1") (pintype "passive"))
      (node (ref "R18") (pin "1") (pinfunction "1_1") (pintype "passive"))
      (node (ref "R19") (pin "1") (pinfunction "1_1") (pintype "passive"))
      (node (ref "U1") (pin "2") (pinfunction "GND_2") (pintype "passive"))
      (node (ref "U10") (pin "4") (pinfunction "GND1_4") (pintype "passive"))
      (node (ref "U6") (pin "14") (pinfunction "VSSA_14") (pintype "passive"))
      (node (ref "U6") (pin "16") (pinfunction "VSS_16") (pintype "passive"))
      (node (ref "U6") (pin "32") (pinfunction "VSS_32") (pintype "passive"))
      (node (ref "U7") (pin "1") (pinfunction "1_1") (pintype "passive"))
      (node (ref "U8") (pin "1") (pinfunction "1_1") (pintype "passive"))
      (node (ref "U9") (pin "1") (pinfunction "1_1") (pintype "passive"))
      (node (ref "USB1") (pin "5") (pinfunction "GND_5") (pintype "passive"))
      (node (ref "USB1") (pin "6") (pinfunction "S_6") (pintype "passive"))
    )
    (net (code "36") (name "Net-(H1-Pad2)") (class "Default")
      (node (ref "H1") (pin "2") (pinfunction "2_2") (pintype "passive"))
      (node (ref "H2") (pin "1") (pinfunction "1_1") (pintype "passive"))
    )
    (net (code "37") (name "Net-(LED1-Pad2)") (class "Default")
      (node (ref "LED1") (pin "2") (pinfunction "2_2") (pintype "passive"))
      (node (ref "R16") (pin "2") (pinfunction "2_2") (pintype "passive"))
    )
    (net (code "38") (name "Net-(LED2-Pad2)") (class "Default")
      (node (ref "LED2") (pin "2") (pinfunction "2_2") (pintype "passive"))
      (node (ref "R18") (pin "2") (pinfunction "2_2") (pintype "passive"))
    )
    (net (code "39") (name "Net-(LED3-Pad2)") (class "Default")
      (node (ref "LED3") (pin "2") (pinfunction "2_2") (pintype "passive"))
      (node (ref "R19") (pin "2") (pinfunction "2_2") (pintype "passive"))
    )
    (net (code "40") (name "Net-(Q3-D_1)") (class "Default")
      (node (ref "J10") (pin "1") (pinfunction "1_1") (pintype "passive"))
      (node (ref "Q3") (pin "5") (pinfunction "D_1_5") (pintype "passive"))
      (node (ref "Q3") (pin "6") (pinfunction "D_2_6") (pintype "passive"))
    )
    (net (code "41") (name "Net-(Q3-G)") (class "Default")
      (node (ref "Q3") (pin "4") (pinfunction "G_4") (pintype "passive"))
      (node (ref "R13") (pin "2") (pinfunction "2_2") (pintype "passive"))
      (node (ref "ZD1") (pin "2") (pinfunction "A_2") (pintype "passive"))
    )
    (net (code "42") (name "Net-(U3-CPH)") (class "Default")
      (node (ref "C11") (pin "2") (pinfunction "2_2") (pintype "passive"))
      (node (ref "U3") (pin "13") (pinfunction "CPH_13") (pintype "passive"))
    )
    (net (code "43") (name "Net-(U3-CPL)") (class "Default")
      (node (ref "C11") (pin "1") (pinfunction "1_1") (pintype "passive"))
      (node (ref "U3") (pin "14") (pinfunction "CPL_14") (pintype "passive"))
    )
    (net (code "44") (name "Net-(U3-IPROPI)") (class "Default")
      (node (ref "R5") (pin "2") (pinfunction "2_2") (pintype "passive"))
      (node (ref "U3") (pin "6") (pinfunction "IPROPI_6") (pintype "passive"))
    )
    (net (code "45") (name "Net-(U3-OUT1)") (class "Default")
      (node (ref "J3") (pin "1") (pinfunction "1_1") (pintype "passive"))
      (node (ref "U3") (pin "8") (pinfunction "OUT1_8") (pintype "passive"))
    )
    (net (code "46") (name "Net-(U3-OUT2)") (class "Default")
      (node (ref "J2") (pin "1") (pinfunction "1_1") (pintype "passive"))
      (node (ref "U3") (pin "10") (pinfunction "OUT2_10") (pintype "passive"))
    )
    (net (code "47") (name "Net-(U3-VCP)") (class "Default")
      (node (ref "C12") (pin "1") (pinfunction "1_1") (pintype "passive"))
      (node (ref "U3") (pin "12") (pinfunction "VCP_12") (pintype "passive"))
    )
    (net (code "48") (name "Net-(U3-nFAULT)") (class "Default")
      (node (ref "R6") (pin "2") (pinfunction "2_2") (pintype "passive"))
      (node (ref "U3") (pin "4") (pinfunction "nFAULT_4") (pintype "passive"))
    )
    (net (code "49") (name "Net-(U3-nSLEEP)") (class "Default")
      (node (ref "R7") (pin "2") (pinfunction "2_2") (pintype "passive"))
      (node (ref "U3") (pin "3") (pinfunction "nSLEEP_3") (pintype "passive"))
    )
    (net (code "50") (name "Net-(U4-CPH)") (class "Default")
      (node (ref "C18") (pin "2") (pinfunction "2_2") (pintype "passive"))
      (node (ref "U4") (pin "13") (pinfunction "CPH_13") (pintype "passive"))
    )
    (net (code "51") (name "Net-(U4-CPL)") (class "Default")
      (node (ref "C18") (pin "1") (pinfunction "1_1") (pintype "passive"))
      (node (ref "U4") (pin "14") (pinfunction "CPL_14") (pintype "passive"))
    )
    (net (code "52") (name "Net-(U4-IPROPI)") (class "Default")
      (node (ref "R12") (pin "2") (pinfunction "2_2") (pintype "passive"))
      (node (ref "U4") (pin "6") (pinfunction "IPROPI_6") (pintype "passive"))
    )
    (net (code "53") (name "Net-(U4-OUT1)") (class "Default")
      (node (ref "J4") (pin "1") (pinfunction "1_1") (pintype "passive"))
      (node (ref "U4") (pin "8") (pinfunction "OUT1_8") (pintype "passive"))
    )
    (net (code "54") (name "Net-(U4-OUT2)") (class "Default")
      (node (ref "J5") (pin "1") (pinfunction "1_1") (pintype "passive"))
      (node (ref "U4") (pin "10") (pinfunction "OUT2_10") (pintype "passive"))
    )
    (net (code "55") (name "Net-(U4-VCP)") (class "Default")
      (node (ref "C17") (pin "1") (pinfunction "1_1") (pintype "passive"))
      (node (ref "U4") (pin "12") (pinfunction "VCP_12") (pintype "passive"))
    )
    (net (code "56") (name "Net-(U4-nFAULT)") (class "Default")
      (node (ref "R10") (pin "2") (pinfunction "2_2") (pintype "passive"))
      (node (ref "U4") (pin "4") (pinfunction "nFAULT_4") (pintype "passive"))
    )
    (net (code "57") (name "Net-(U4-nSLEEP)") (class "Default")
      (node (ref "R9") (pin "2") (pinfunction "2_2") (pintype "passive"))
      (node (ref "U4") (pin "3") (pinfunction "nSLEEP_3") (pintype "passive"))
    )
    (net (code "58") (name "Net-(U5-CPH)") (class "Default")
      (node (ref "C23") (pin "2") (pinfunction "2_2") (pintype "passive"))
      (node (ref "U5") (pin "13") (pinfunction "CPH_13") (pintype "passive"))
    )
    (net (code "59") (name "Net-(U5-CPL)") (class "Default")
      (node (ref "C23") (pin "1") (pinfunction "1_1") (pintype "passive"))
      (node (ref "U5") (pin "14") (pinfunction "CPL_14") (pintype "passive"))
    )
    (net (code "60") (name "Net-(U5-IPROPI)") (class "Default")
      (node (ref "R17") (pin "2") (pinfunction "2_2") (pintype "passive"))
      (node (ref "U5") (pin "6") (pinfunction "IPROPI_6") (pintype "passive"))
    )
    (net (code "61") (name "Net-(U5-OUT1)") (class "Default")
      (node (ref "J6") (pin "1") (pinfunction "1_1") (pintype "passive"))
      (node (ref "U5") (pin "8") (pinfunction "OUT1_8") (pintype "passive"))
    )
    (net (code "62") (name "Net-(U5-OUT2)") (class "Default")
      (node (ref "J7") (pin "1") (pinfunction "1_1") (pintype "passive"))
      (node (ref "U5") (pin "10") (pinfunction "OUT2_10") (pintype "passive"))
    )
    (net (code "63") (name "Net-(U5-VCP)") (class "Default")
      (node (ref "C22") (pin "1") (pinfunction "1_1") (pintype "passive"))
      (node (ref "U5") (pin "12") (pinfunction "VCP_12") (pintype "passive"))
    )
    (net (code "64") (name "Net-(U5-nFAULT)") (class "Default")
      (node (ref "R15") (pin "2") (pinfunction "2_2") (pintype "passive"))
      (node (ref "U5") (pin "4") (pinfunction "nFAULT_4") (pintype "passive"))
    )
    (net (code "65") (name "Net-(U5-nSLEEP)") (class "Default")
      (node (ref "R14") (pin "2") (pinfunction "2_2") (pintype "passive"))
      (node (ref "U5") (pin "3") (pinfunction "nSLEEP_3") (pintype "passive"))
    )
    (net (code "66") (name "Net-(U6-PA7)") (class "Default")
      (node (ref "H3") (pin "2") (pinfunction "2_2") (pintype "passive"))
      (node (ref "U6") (pin "12") (pinfunction "PA7_12") (pintype "passive"))
    )
    (net (code "67") (name "Net-(U6-PB3)") (class "Default")
      (node (ref "LED3") (pin "1") (pinfunction "1_1") (pintype "passive"))
      (node (ref "U6") (pin "26") (pinfunction "PB3_26") (pintype "passive"))
    )
    (net (code "68") (name "Net-(U6-PB8-BOOT0)") (class "Default")
      (node (ref "R11") (pin "2") (pinfunction "2_2") (pintype "passive"))
      (node (ref "U6") (pin "31") (pinfunction "PB8-BOOT0_31") (pintype "passive"))
    )
    (net (code "69") (name "Net-(U6-PBO)") (class "Default")
      (node (ref "H3") (pin "1") (pinfunction "1_1") (pintype "passive"))
      (node (ref "U6") (pin "13") (pinfunction "PBO_13") (pintype "passive"))
    )
    (net (code "70") (name "VCC(MB)") (class "Default")
      (node (ref "C12") (pin "2") (pinfunction "2_2") (pintype "passive"))
      (node (ref "C13") (pin "2") (pinfunction "2_2") (pintype "passive"))
      (node (ref "C14") (pin "2") (pinfunction "2_2") (pintype "passive"))
      (node (ref "C15") (pin "2") (pinfunction "2_2") (pintype "passive"))
      (node (ref "C16") (pin "2") (pinfunction "2_2") (pintype "passive"))
      (node (ref "C17") (pin "2") (pinfunction "2_2") (pintype "passive"))
      (node (ref "C20") (pin "2") (pinfunction "2_2") (pintype "passive"))
      (node (ref "C21") (pin "2") (pinfunction "2_2") (pintype "passive"))
      (node (ref "C22") (pin "2") (pinfunction "2_2") (pintype "passive"))
      (node (ref "C5") (pin "1") (pinfunction "1_1") (pintype "passive"))
      (node (ref "C6") (pin "1") (pinfunction "1_1") (pintype "passive"))
      (node (ref "C7") (pin "2") (pinfunction "2_2") (pintype "passive"))
      (node (ref "Q3") (pin "1") (pinfunction "S_1_1") (pintype "passive"))
      (node (ref "Q3") (pin "2") (pinfunction "S_2_2") (pintype "passive"))
      (node (ref "Q3") (pin "3") (pinfunction "S_3_3") (pintype "passive"))
      (node (ref "U2") (pin "1") (pinfunction "IN_1") (pintype "passive"))
      (node (ref "U3") (pin "11") (pinfunction "VM_11") (pintype "passive"))
      (node (ref "U4") (pin "11") (pinfunction "VM_11") (pintype "passive"))
      (node (ref "U5") (pin "11") (pinfunction "VM_11") (pintype "passive"))
      (node (ref "ZD1") (pin "1") (pinfunction "K_1") (pintype "passive"))
    )
    (net (code "71") (name "unconnected-(J8-RX-Pad7)") (class "Default")
      (node (ref "J8") (pin "7") (pinfunction "RX_7") (pintype "passive"))
    )
    (net (code "72") (name "unconnected-(J8-SWO-Pad6)") (class "Default")
      (node (ref "J8") (pin "6") (pinfunction "SWO_6") (pintype "passive"))
    )
    (net (code "73") (name "unconnected-(J8-TDI-Pad8)") (class "Default")
      (node (ref "J8") (pin "8") (pinfunction "TDI_8") (pintype "passive"))
    )
    (net (code "74") (name "unconnected-(U1-NC-Pad4)") (class "Default")
      (node (ref "U1") (pin "4") (pinfunction "NC_4") (pintype "passive"))
    )
    (net (code "75") (name "unconnected-(U2-EN-Pad3)") (class "Default")
      (node (ref "U2") (pin "3") (pinfunction "EN_3") (pintype "passive"))
    )
    (net (code "76") (name "unconnected-(U2-NC-Pad4)") (class "Default")
      (node (ref "U2") (pin "4") (pinfunction "NC_4") (pintype "passive"))
    )
    (net (code "77") (name "unconnected-(U6-PB5-Pad28)") (class "Default")
      (node (ref "U6") (pin "28") (pinfunction "PB5_28") (pintype "passive"))
    )
    (net (code "78") (name "unconnected-(U6-PF0-OSC_IN-Pad2)") (class "Default")
      (node (ref "U6") (pin "2") (pinfunction "PF0-OSC_IN_2") (pintype "passive"))
    )
    (net (code "79") (name "unconnected-(U6-PF1-OSC_OUT-Pad3)") (class "Default")
      (node (ref "U6") (pin "3") (pinfunction "PF1-OSC_OUT_3") (pintype "passive"))
    )
    (net (code "80") (name "unconnected-(U11-Pad3)") (class "Default")
      (node (ref "U11") (pin "3") (pinfunction "3_3") (pintype "passive"))
    )
    (net (code "81") (name "unconnected-(U11-Pad4)") (class "Default")
      (node (ref "U11") (pin "4") (pinfunction "4_4") (pintype "passive"))
    )
    (net (code "82") (name "unconnected-(USB1-ID-Pad4)") (class "Default")
      (node (ref "USB1") (pin "4") (pinfunction "ID_4") (pintype "passive"))
    )
  )
)
